# untitled.net
KiCad netlist of a schematic drawn in EAGLE
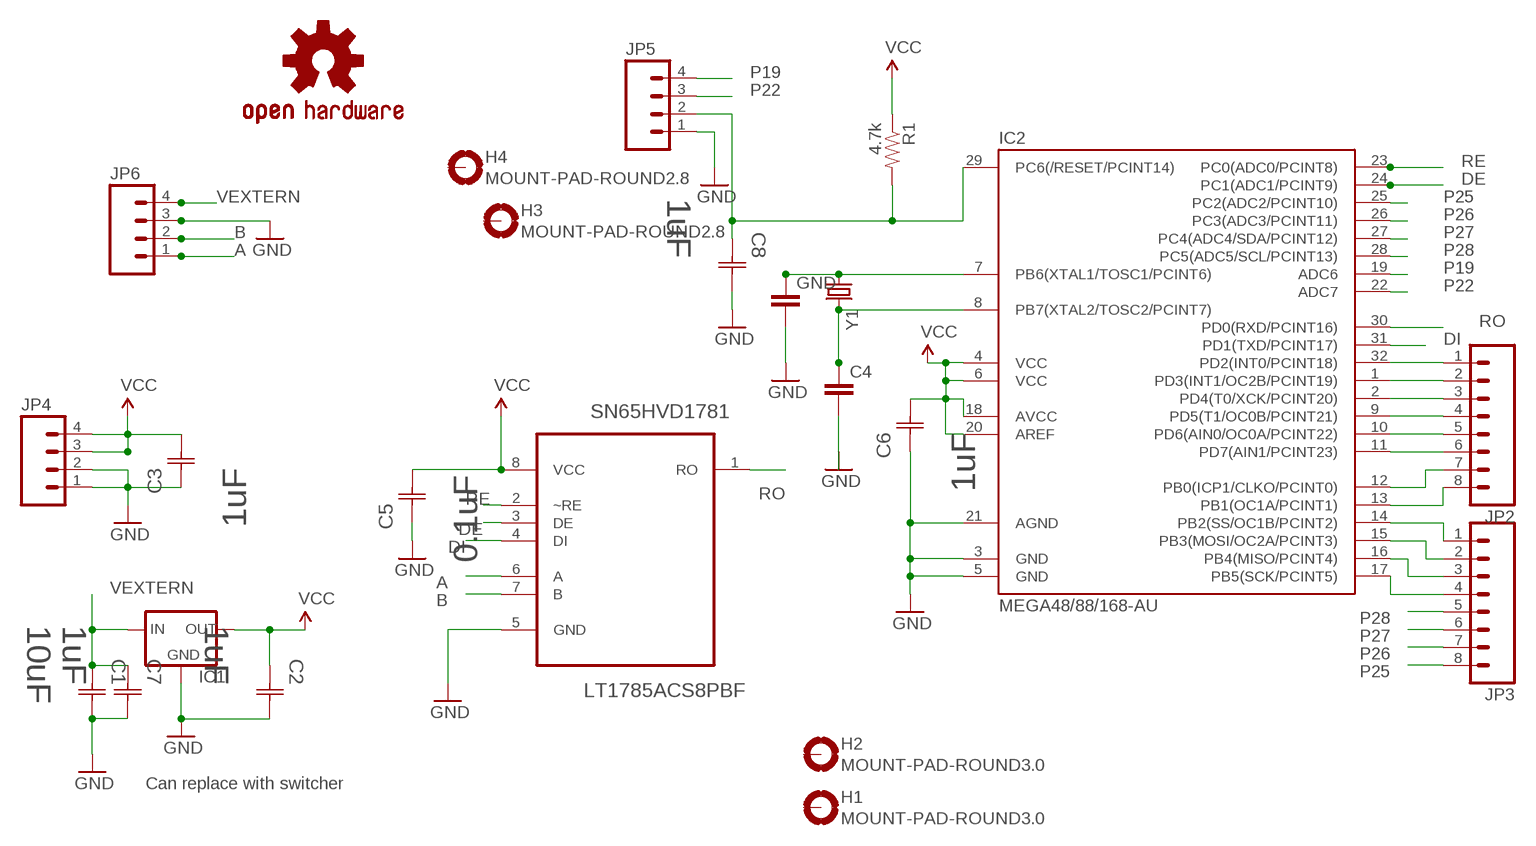
[diagram p0: schematic, sheet 1]

(export (version "E")
  (design (tool "Eeschema 10.0.6"))
  (components
    (comp (ref "C1")
      (value "10uF")
      (footprint "eagle-import:CAPC3225X270N")
      (fields (field (name "MPN") "GRM32ER7YA106KA12L") (field (name "TOLERANCE") "±10%"))
      (libsource (lib "eagle-import") (part "GRM32ER7YA106KA12L"))
    )
    (comp (ref "C2")
      (value "1uF")
      (footprint "eagle-import:CAPC2013X135N")
      (fields (field (name "MPN") "GRM21BR71H105KA12L ") (field (name "TOLERANCE") "±10%"))
      (libsource (lib "eagle-import") (part "GRM21BR71H105KA12L"))
    )
    (comp (ref "C3")
      (value "1uF")
      (footprint "eagle-import:CAPC2013X135N")
      (fields
        (field (name "MPN") "GRM21BR71H105KA12L ")
        (field (name "TOLERANCE") "±10%")
        (field (name "MPN_1") "GRM21BR71H105KA12L ")
        (field (name "OC_FARNELL") "1735541")
        (field (name "OC_NEWARK") "24R6342")
        (field (name "SUPPLIER") "Murata")
        (field (name "TOLERANCE_1") "±10%")
        (field (name "VOLTAGERATING") "50V")
      )
      (libsource (lib "eagle-import") (part "GRM21BR71H105KA12L"))
    )
    (comp (ref "C4")
      (value "CAP0805")
      (footprint "eagle-import:0805")
      (libsource (lib "eagle-import") (part "CAP0805"))
    )
    (comp (ref "C5")
      (value "0.1uF")
      (footprint "eagle-import:CAPC2013X135N")
      (fields
        (field (name "MPN") "GRM21BR71H105KA12L ")
        (field (name "TOLERANCE") "±10%")
        (field (name "MPN_1") "GRM21BR71H105KA12L ")
        (field (name "OC_FARNELL") "1735541")
        (field (name "OC_NEWARK") "24R6342")
        (field (name "SUPPLIER") "Murata")
        (field (name "TOLERANCE_1") "±10%")
        (field (name "VOLTAGERATING") "50V")
      )
      (libsource (lib "eagle-import") (part "GRM21BR71H105KA12L"))
    )
    (comp (ref "C6")
      (value "1uF")
      (footprint "eagle-import:CAPC2013X135N")
      (fields
        (field (name "MPN") "GRM21BR71H105KA12L ")
        (field (name "TOLERANCE") "±10%")
        (field (name "MPN_1") "GRM21BR71H105KA12L ")
        (field (name "OC_FARNELL") "1735541")
        (field (name "OC_NEWARK") "24R6342")
        (field (name "SUPPLIER") "Murata")
        (field (name "TOLERANCE_1") "±10%")
        (field (name "VOLTAGERATING") "50V")
      )
      (libsource (lib "eagle-import") (part "GRM21BR71H105KA12L"))
    )
    (comp (ref "C7")
      (value "1uF")
      (footprint "eagle-import:CAPC2013X135N")
      (fields
        (field (name "MPN") "GRM21BR71H105KA12L ")
        (field (name "TOLERANCE") "±10%")
        (field (name "MPN_1") "GRM21BR71H105KA12L ")
        (field (name "OC_FARNELL") "1735541")
        (field (name "OC_NEWARK") "24R6342")
        (field (name "SUPPLIER") "Murata")
        (field (name "TOLERANCE_1") "±10%")
        (field (name "VOLTAGERATING") "50V")
      )
      (libsource (lib "eagle-import") (part "GRM21BR71H105KA12L"))
    )
    (comp (ref "C8")
      (value "1uF")
      (footprint "eagle-import:CAPC2013X135N")
      (fields
        (field (name "MPN") "GRM21BR71H105KA12L ")
        (field (name "TOLERANCE") "±10%")
        (field (name "MPN_1") "GRM21BR71H105KA12L ")
        (field (name "OC_FARNELL") "1735541")
        (field (name "OC_NEWARK") "24R6342")
        (field (name "SUPPLIER") "Murata")
        (field (name "TOLERANCE_1") "±10%")
        (field (name "VOLTAGERATING") "50V")
      )
      (libsource (lib "eagle-import") (part "GRM21BR71H105KA12L"))
    )
    (comp (ref "GND")
      (value "CAP0805")
      (footprint "eagle-import:0805")
      (libsource (lib "eagle-import") (part "CAP0805"))
    )
    (comp (ref "H1")
      (value "MOUNT-PAD-ROUND3.0")
      (footprint "eagle-import:3,0-PAD")
      (libsource (lib "eagle-import") (part "MOUNT-PAD-ROUND3.0"))
    )
    (comp (ref "H2")
      (value "MOUNT-PAD-ROUND3.0")
      (footprint "eagle-import:3,0-PAD")
      (libsource (lib "eagle-import") (part "MOUNT-PAD-ROUND3.0"))
    )
    (comp (ref "H3")
      (value "MOUNT-PAD-ROUND2.8")
      (footprint "eagle-import:2,8-PAD")
      (libsource (lib "eagle-import") (part "MOUNT-PAD-ROUND2.8"))
    )
    (comp (ref "H4")
      (value "MOUNT-PAD-ROUND2.8")
      (footprint "eagle-import:2,8-PAD")
      (libsource (lib "eagle-import") (part "MOUNT-PAD-ROUND2.8"))
    )
    (comp (ref "IC1")
      (value "V_REG_78XXSIDE")
      (footprint "eagle-import:78XXL")
      (libsource (lib "eagle-import") (part "V_REG_78XXSIDE"))
    )
    (comp (ref "IC2")
      (value "MEGA48/88/168-AU")
      (footprint "eagle-import:TQFP32-08")
      (libsource (lib "eagle-import") (part "MEGA48/88/168-AU"))
    )
    (comp (ref "JP2")
      (value "M08LOCK")
      (footprint "eagle-import:1X08_LOCK")
      (libsource (lib "eagle-import") (part "M08LOCK"))
    )
    (comp (ref "JP3")
      (value "M08LOCK")
      (footprint "eagle-import:1X08_LOCK")
      (libsource (lib "eagle-import") (part "M08LOCK"))
    )
    (comp (ref "JP4")
      (value "M04PTH")
      (footprint "eagle-import:1X04")
      (libsource (lib "eagle-import") (part "M04PTH"))
    )
    (comp (ref "JP5")
      (value "M04LOCK")
      (footprint "eagle-import:1X04_LOCK")
      (libsource (lib "eagle-import") (part "M04LOCK"))
    )
    (comp (ref "JP6")
      (value "M04SCREW")
      (footprint "eagle-import:SCREWTERMINAL-3.5MM-4")
      (libsource (lib "eagle-import") (part "M04SCREW"))
    )
    (comp (ref "R1")
      (value "4.7k")
      (footprint "eagle-import:0805")
      (libsource (lib "eagle-import") (part "RESISTOR0805-RES"))
    )
    (comp (ref "SN65HVD1781")
      (value "LT1785ACS8PBF")
      (footprint "eagle-import:SOIC127P600X175-8N")
      (fields (field (name "MPN") "LT1785ACS8#PBF"))
      (libsource (lib "eagle-import") (part "LT1785ACS8PBF"))
    )
    (comp (ref "U$1")
      (value "OSHW-LOGOM")
      (footprint "eagle-import:OSHW-LOGO-M")
      (libsource (lib "eagle-import") (part "OSHW-LOGOM"))
    )
    (comp (ref "Y1")
      (value "CRYSTALSMD")
      (footprint "eagle-import:HC49UP")
      (libsource (lib "eagle-import") (part "CRYSTALSMD"))
    )
  )
  (nets
    (net (code "1") (name "/A") (class "Default")
      (node (ref "JP6") (pin "1") (pinfunction "1_1") (pintype "passive"))
      (node (ref "SN65HVD1781") (pin "6") (pinfunction "A_6") (pintype "input"))
    )
    (net (code "2") (name "/B") (class "Default")
      (node (ref "JP6") (pin "2") (pinfunction "2_2") (pintype "passive"))
      (node (ref "SN65HVD1781") (pin "7") (pinfunction "B_7") (pintype "input"))
    )
    (net (code "3") (name "/DE") (class "Default")
      (node (ref "IC2") (pin "24") (pinfunction "PC1(ADC1/PCINT9)_24") (pintype "bidirectional"))
      (node (ref "SN65HVD1781") (pin "3") (pinfunction "DE_3") (pintype "input"))
    )
    (net (code "4") (name "/DI") (class "Default")
      (node (ref "IC2") (pin "31") (pinfunction "PD1(TXD/PCINT17)_31") (pintype "bidirectional"))
      (node (ref "SN65HVD1781") (pin "4") (pinfunction "DI_4") (pintype "input"))
    )
    (net (code "5") (name "/P19") (class "Default")
      (node (ref "IC2") (pin "19") (pinfunction "ADC6_19") (pintype "passive"))
      (node (ref "JP5") (pin "4") (pinfunction "4_4") (pintype "passive"))
    )
    (net (code "6") (name "/P22") (class "Default")
      (node (ref "IC2") (pin "22") (pinfunction "ADC7_22") (pintype "passive"))
      (node (ref "JP5") (pin "3") (pinfunction "3_3") (pintype "passive"))
    )
    (net (code "7") (name "/P25") (class "Default")
      (node (ref "IC2") (pin "25") (pinfunction "PC2(ADC2/PCINT10)_25") (pintype "bidirectional"))
      (node (ref "JP3") (pin "8") (pinfunction "8_8") (pintype "passive"))
    )
    (net (code "8") (name "/P26") (class "Default")
      (node (ref "IC2") (pin "26") (pinfunction "PC3(ADC3/PCINT11)_26") (pintype "bidirectional"))
      (node (ref "JP3") (pin "7") (pinfunction "7_7") (pintype "passive"))
    )
    (net (code "9") (name "/P27") (class "Default")
      (node (ref "IC2") (pin "27") (pinfunction "PC4(ADC4/SDA/PCINT12)_27") (pintype "bidirectional"))
      (node (ref "JP3") (pin "6") (pinfunction "6_6") (pintype "passive"))
    )
    (net (code "10") (name "/P28") (class "Default")
      (node (ref "IC2") (pin "28") (pinfunction "PC5(ADC5/SCL/PCINT13)_28") (pintype "bidirectional"))
      (node (ref "JP3") (pin "5") (pinfunction "5_5") (pintype "passive"))
    )
    (net (code "11") (name "/RE") (class "Default")
      (node (ref "IC2") (pin "23") (pinfunction "PC0(ADC0/PCINT8)_23") (pintype "bidirectional"))
      (node (ref "SN65HVD1781") (pin "2") (pinfunction "~{RE}_2") (pintype "input"))
    )
    (net (code "12") (name "/RO") (class "Default")
      (node (ref "IC2") (pin "30") (pinfunction "PD0(RXD/PCINT16)_30") (pintype "bidirectional"))
      (node (ref "SN65HVD1781") (pin "1") (pinfunction "RO_1") (pintype "output"))
    )
    (net (code "13") (name "/VEXTERN") (class "Default")
      (node (ref "C1") (pin "1") (pinfunction "C1_1") (pintype "passive"))
      (node (ref "C7") (pin "1") (pinfunction "C1_1") (pintype "passive"))
      (node (ref "IC1") (pin "IN") (pinfunction "IN_IN") (pintype "input"))
      (node (ref "JP6") (pin "4") (pinfunction "4_4") (pintype "passive"))
    )
    (net (code "14") (name "GND") (class "Default")
      (node (ref "C1") (pin "2") (pinfunction "C2_2") (pintype "passive"))
      (node (ref "C2") (pin "2") (pinfunction "C2_2") (pintype "passive"))
      (node (ref "C3") (pin "1") (pinfunction "C1_1") (pintype "passive"))
      (node (ref "C4") (pin "2") (pinfunction "2_2") (pintype "passive"))
      (node (ref "C5") (pin "1") (pinfunction "C1_1") (pintype "passive"))
      (node (ref "C6") (pin "1") (pinfunction "C1_1") (pintype "passive"))
      (node (ref "C7") (pin "2") (pinfunction "C2_2") (pintype "passive"))
      (node (ref "C8") (pin "2") (pinfunction "C2_2") (pintype "passive"))
      (node (ref "GND") (pin "2") (pinfunction "2_2") (pintype "passive"))
      (node (ref "IC1") (pin "GND") (pinfunction "GND_GND") (pintype "input"))
      (node (ref "IC2") (pin "21") (pinfunction "AGND_21") (pintype "power_in"))
      (node (ref "IC2") (pin "3") (pinfunction "GND_3") (pintype "power_in"))
      (node (ref "IC2") (pin "5") (pinfunction "GND_5") (pintype "power_in"))
      (node (ref "JP4") (pin "1") (pinfunction "1_1") (pintype "passive"))
      (node (ref "JP4") (pin "2") (pinfunction "2_2") (pintype "passive"))
      (node (ref "JP5") (pin "1") (pinfunction "1_1") (pintype "passive"))
      (node (ref "JP6") (pin "3") (pinfunction "3_3") (pintype "passive"))
      (node (ref "SN65HVD1781") (pin "5") (pinfunction "GND_5") (pintype "passive"))
    )
    (net (code "15") (name "Net-(C8-C1)") (class "Default")
      (node (ref "C8") (pin "1") (pinfunction "C1_1") (pintype "passive"))
      (node (ref "IC2") (pin "29") (pinfunction "PC6(/RESET/PCINT14)_29") (pintype "bidirectional"))
      (node (ref "JP5") (pin "2") (pinfunction "2_2") (pintype "passive"))
      (node (ref "R1") (pin "2") (pinfunction "2_2") (pintype "passive"))
    )
    (net (code "16") (name "Net-(IC2-PB0(ICP1{slash}CLKO{slash}PCINT0))") (class "Default")
      (node (ref "IC2") (pin "12") (pinfunction "PB0(ICP1/CLKO/PCINT0)_12") (pintype "bidirectional"))
      (node (ref "JP2") (pin "7") (pinfunction "7_7") (pintype "passive"))
    )
    (net (code "17") (name "Net-(IC2-PB1(OC1A{slash}PCINT1))") (class "Default")
      (node (ref "IC2") (pin "13") (pinfunction "PB1(OC1A/PCINT1)_13") (pintype "bidirectional"))
      (node (ref "JP2") (pin "8") (pinfunction "8_8") (pintype "passive"))
    )
    (net (code "18") (name "Net-(IC2-PB2(SS{slash}OC1B{slash}PCINT2))") (class "Default")
      (node (ref "IC2") (pin "14") (pinfunction "PB2(SS/OC1B/PCINT2)_14") (pintype "bidirectional"))
      (node (ref "JP3") (pin "1") (pinfunction "1_1") (pintype "passive"))
    )
    (net (code "19") (name "Net-(IC2-PB3(MOSI{slash}OC2A{slash}PCINT3))") (class "Default")
      (node (ref "IC2") (pin "15") (pinfunction "PB3(MOSI/OC2A/PCINT3)_15") (pintype "bidirectional"))
      (node (ref "JP3") (pin "2") (pinfunction "2_2") (pintype "passive"))
    )
    (net (code "20") (name "Net-(IC2-PB4(MISO{slash}PCINT4))") (class "Default")
      (node (ref "IC2") (pin "16") (pinfunction "PB4(MISO/PCINT4)_16") (pintype "bidirectional"))
      (node (ref "JP3") (pin "3") (pinfunction "3_3") (pintype "passive"))
    )
    (net (code "21") (name "Net-(IC2-PB5(SCK{slash}PCINT5))") (class "Default")
      (node (ref "IC2") (pin "17") (pinfunction "PB5(SCK/PCINT5)_17") (pintype "bidirectional"))
      (node (ref "JP3") (pin "4") (pinfunction "4_4") (pintype "passive"))
    )
    (net (code "22") (name "Net-(IC2-PB6(XTAL1{slash}TOSC1{slash}PCINT6))") (class "Default")
      (node (ref "GND") (pin "1") (pinfunction "1_1") (pintype "passive"))
      (node (ref "IC2") (pin "7") (pinfunction "PB6(XTAL1/TOSC1/PCINT6)_7") (pintype "bidirectional"))
      (node (ref "Y1") (pin "1") (pinfunction "1_1") (pintype "passive"))
    )
    (net (code "23") (name "Net-(IC2-PB7(XTAL2{slash}TOSC2{slash}PCINT7))") (class "Default")
      (node (ref "C4") (pin "1") (pinfunction "1_1") (pintype "passive"))
      (node (ref "IC2") (pin "8") (pinfunction "PB7(XTAL2/TOSC2/PCINT7)_8") (pintype "bidirectional"))
      (node (ref "Y1") (pin "2") (pinfunction "2_2") (pintype "passive"))
    )
    (net (code "24") (name "Net-(IC2-PD2(INT0{slash}PCINT18))") (class "Default")
      (node (ref "IC2") (pin "32") (pinfunction "PD2(INT0/PCINT18)_32") (pintype "bidirectional"))
      (node (ref "JP2") (pin "1") (pinfunction "1_1") (pintype "passive"))
    )
    (net (code "25") (name "Net-(IC2-PD3(INT1{slash}OC2B{slash}PCINT19))") (class "Default")
      (node (ref "IC2") (pin "1") (pinfunction "PD3(INT1/OC2B/PCINT19)_1") (pintype "bidirectional"))
      (node (ref "JP2") (pin "2") (pinfunction "2_2") (pintype "passive"))
    )
    (net (code "26") (name "Net-(IC2-PD4(T0{slash}XCK{slash}PCINT20))") (class "Default")
      (node (ref "IC2") (pin "2") (pinfunction "PD4(T0/XCK/PCINT20)_2") (pintype "bidirectional"))
      (node (ref "JP2") (pin "3") (pinfunction "3_3") (pintype "passive"))
    )
    (net (code "27") (name "Net-(IC2-PD5(T1{slash}OC0B{slash}PCINT21))") (class "Default")
      (node (ref "IC2") (pin "9") (pinfunction "PD5(T1/OC0B/PCINT21)_9") (pintype "bidirectional"))
      (node (ref "JP2") (pin "4") (pinfunction "4_4") (pintype "passive"))
    )
    (net (code "28") (name "Net-(IC2-PD6(AIN0{slash}OC0A{slash}PCINT22))") (class "Default")
      (node (ref "IC2") (pin "10") (pinfunction "PD6(AIN0/OC0A/PCINT22)_10") (pintype "bidirectional"))
      (node (ref "JP2") (pin "5") (pinfunction "5_5") (pintype "passive"))
    )
    (net (code "29") (name "Net-(IC2-PD7(AIN1{slash}PCINT23))") (class "Default")
      (node (ref "IC2") (pin "11") (pinfunction "PD7(AIN1/PCINT23)_11") (pintype "bidirectional"))
      (node (ref "JP2") (pin "6") (pinfunction "6_6") (pintype "passive"))
    )
    (net (code "30") (name "VCC") (class "Default")
      (node (ref "C2") (pin "1") (pinfunction "C1_1") (pintype "passive"))
      (node (ref "C3") (pin "2") (pinfunction "C2_2") (pintype "passive"))
      (node (ref "C5") (pin "2") (pinfunction "C2_2") (pintype "passive"))
      (node (ref "C6") (pin "2") (pinfunction "C2_2") (pintype "passive"))
      (node (ref "IC1") (pin "OUT") (pinfunction "OUT_OUT") (pintype "output"))
      (node (ref "IC2") (pin "18") (pinfunction "AVCC_18") (pintype "passive"))
      (node (ref "IC2") (pin "20") (pinfunction "AREF_20") (pintype "passive"))
      (node (ref "IC2") (pin "4") (pinfunction "VCC_4") (pintype "power_in"))
      (node (ref "IC2") (pin "6") (pinfunction "VCC_6") (pintype "power_in"))
      (node (ref "JP4") (pin "3") (pinfunction "3_3") (pintype "passive"))
      (node (ref "JP4") (pin "4") (pinfunction "4_4") (pintype "passive"))
      (node (ref "R1") (pin "1") (pinfunction "1_1") (pintype "passive"))
      (node (ref "SN65HVD1781") (pin "8") (pinfunction "VCC_8") (pintype "power_in"))
    )
    (net (code "31") (name "unconnected-(H1-MOUNT-PadB3,0)") (class "Default")
      (node (ref "H1") (pin "B3,0") (pinfunction "MOUNT_B3,0") (pintype "passive"))
    )
    (net (code "32") (name "unconnected-(H2-MOUNT-PadB3,0)") (class "Default")
      (node (ref "H2") (pin "B3,0") (pinfunction "MOUNT_B3,0") (pintype "passive"))
    )
    (net (code "33") (name "unconnected-(H3-MOUNT-PadB2,8)") (class "Default")
      (node (ref "H3") (pin "B2,8") (pinfunction "MOUNT_B2,8") (pintype "passive"))
    )
    (net (code "34") (name "unconnected-(H4-MOUNT-PadB2,8)") (class "Default")
      (node (ref "H4") (pin "B2,8") (pinfunction "MOUNT_B2,8") (pintype "passive"))
    )
  )
)
